# Shutdown.net
KiCad netlist of a schematic drawn in Altium Designer
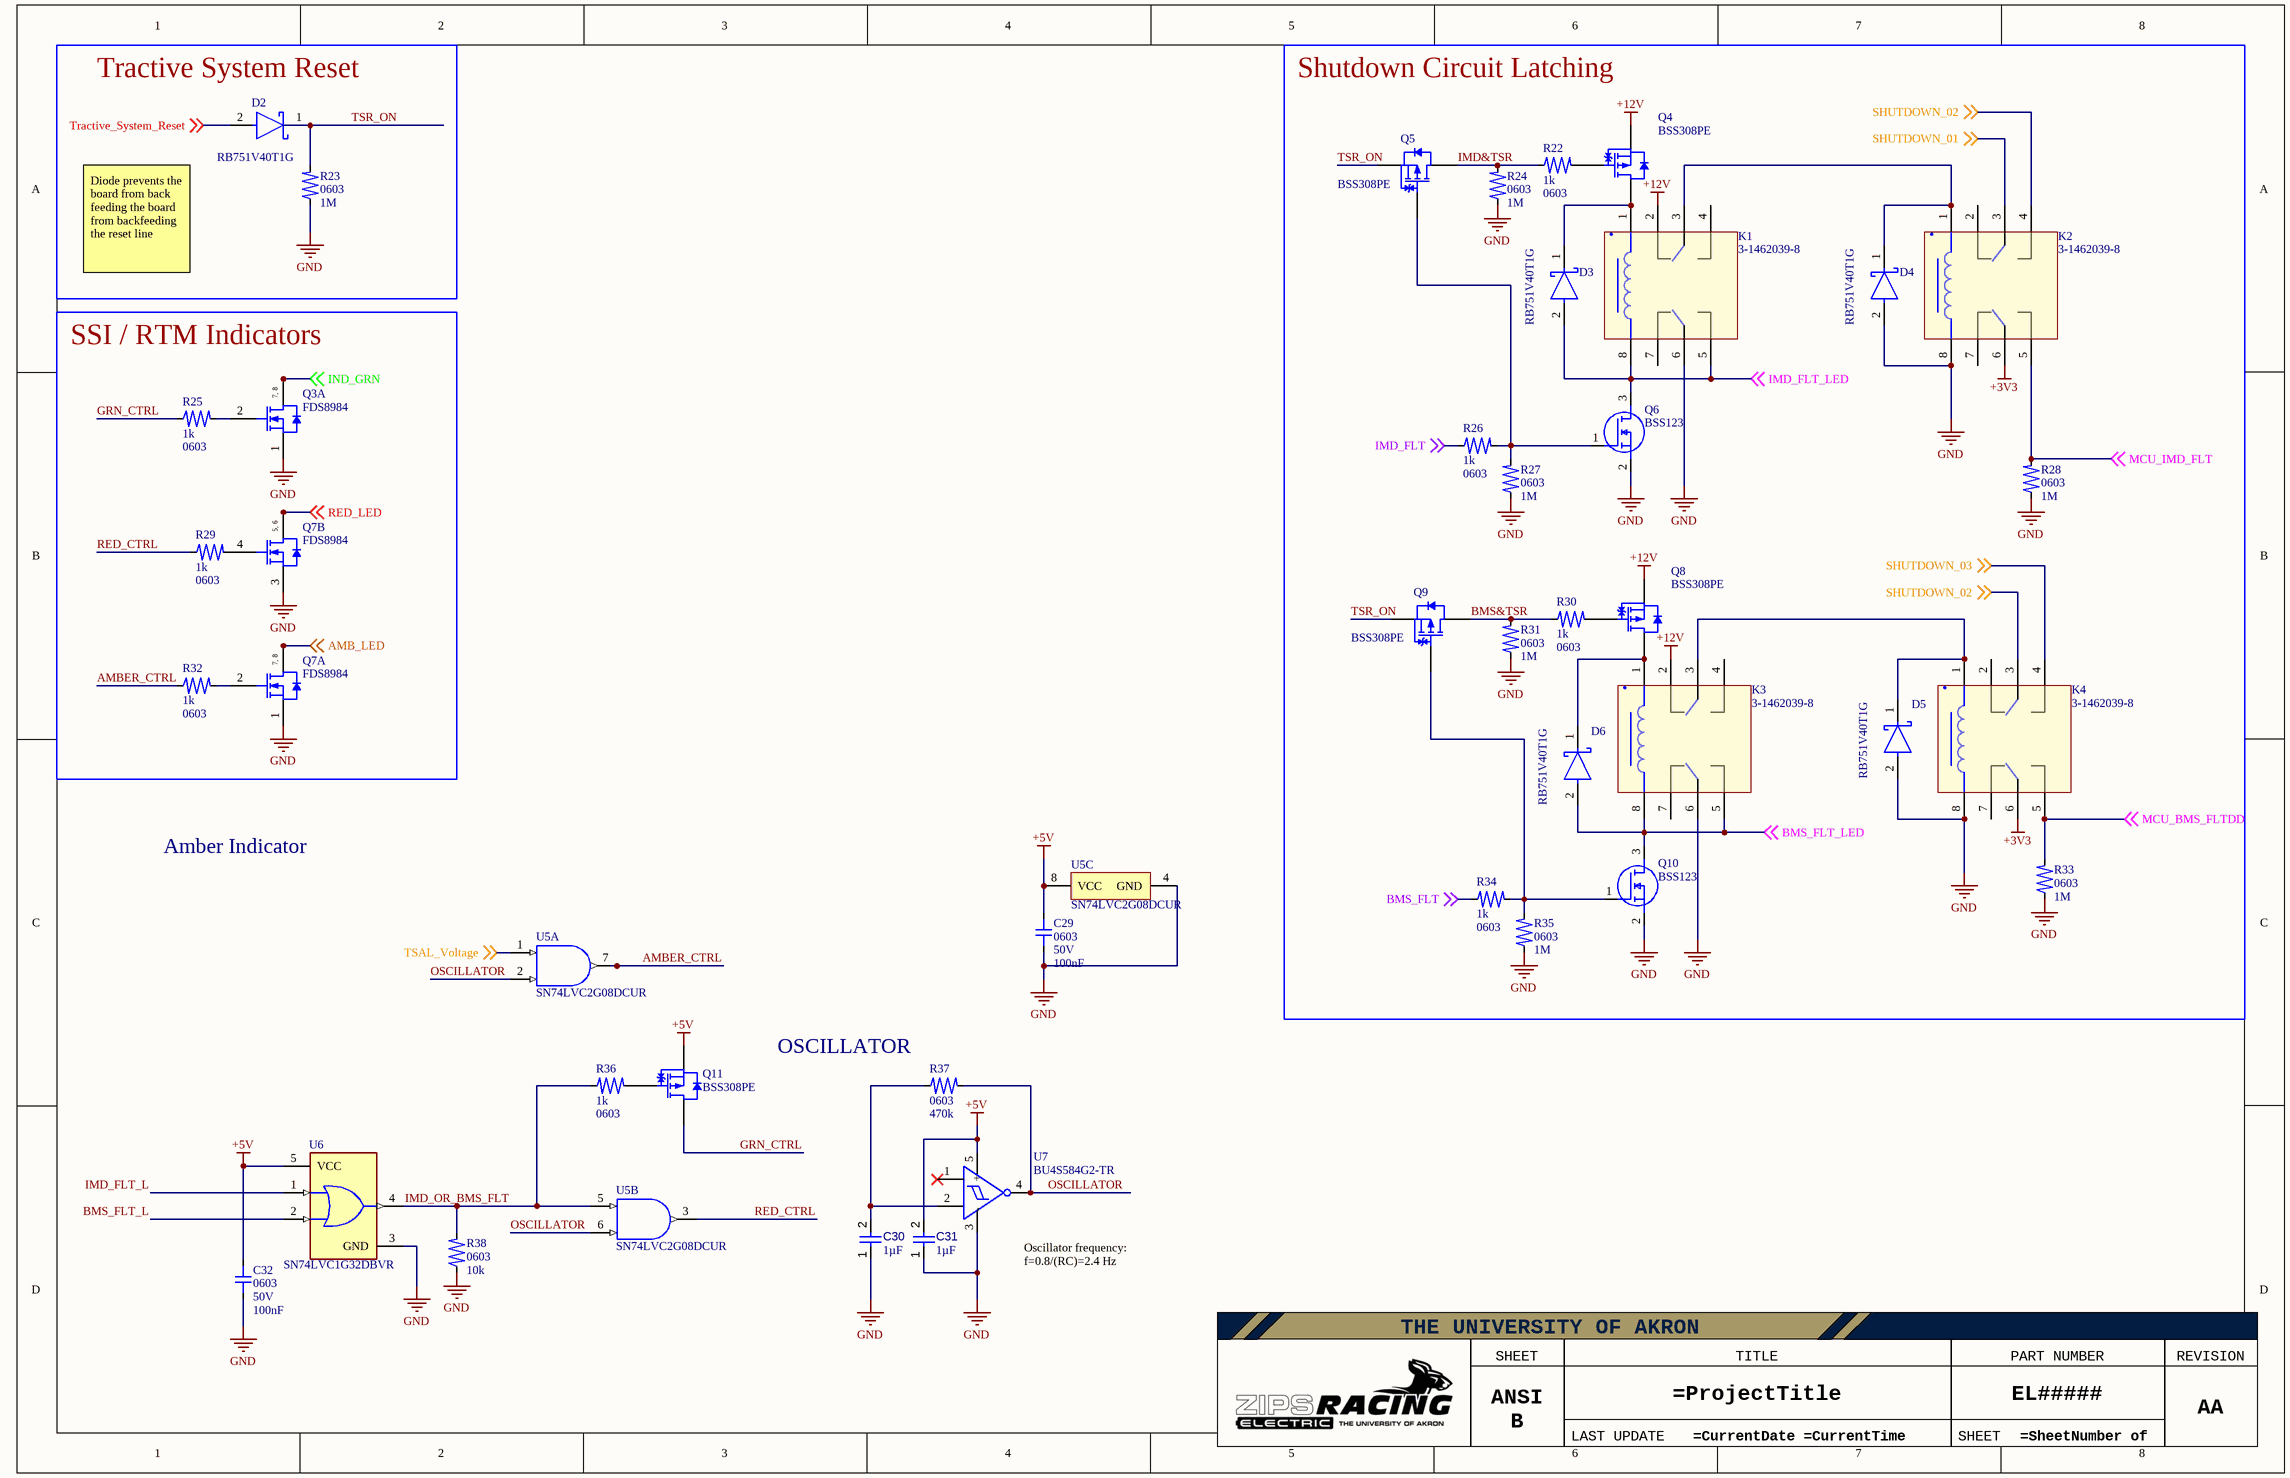
[diagram p0: Shutdown.SchDoc]

(export (version "E")
  (design (tool "Eeschema 10.0.6"))
  (components
    (comp (ref "C29")
      (value "100nF")
      (footprint "0603")
      (description "Capacitor, 0603, 5%")
      (fields (field (name "VOLTAGE") "50V") (field (name "Comment") "Capacitor 100nF 0603 5%"))
      (libsource (lib "Zips Racing Electric") (part "CAP-0603"))
    )
    (comp (ref "C30")
      (value "1µF")
      (footprint "CAPC1608X94X35NL15T15")
      (description "Chip Capacitor, 1 uF, +/- 10%, 16 V, 0603 (1608 Metric)")
      (fields (field (name "TOLERANCE") "10%") (field (name "Comment") "Capacitor 1 uF +/- 10% 16 V 0603"))
      (libsource (lib "Zips Racing Electric") (part "CAP-NP-2"))
    )
    (comp (ref "C31")
      (value "1µF")
      (footprint "CAPC1608X94X35NL15T15")
      (description "Chip Capacitor, 1 uF, +/- 10%, 16 V, 0603 (1608 Metric)")
      (fields (field (name "TOLERANCE") "10%") (field (name "Comment") "Capacitor 1 uF +/- 10% 16 V 0603"))
      (libsource (lib "Zips Racing Electric") (part "CAP-NP-2"))
    )
    (comp (ref "C32")
      (value "100nF")
      (footprint "0603")
      (description "Capacitor, 0603, 5%")
      (fields (field (name "VOLTAGE") "50V") (field (name "Comment") "Capacitor 100nF 0603 5%"))
      (libsource (lib "Zips Racing Electric") (part "CAP-0603"))
    )
    (comp (ref "D2")
      (value "RB751V40T1G")
      (footprint "FP-477-02-MFG")
      (description "Rectifier Diode, Schottky, 1 Phase, 1 Element, 0.03A, 40V V(RRM), Silicon")
      (libsource (lib "Zips Racing Electric") (part "1d6ec82d83fb6aee721767c19dac4b9"))
    )
    (comp (ref "D3")
      (value "RB751V40T1G")
      (footprint "FP-477-02-MFG")
      (description "Rectifier Diode, Schottky, 1 Phase, 1 Element, 0.03A, 40V V(RRM), Silicon")
      (libsource (lib "Zips Racing Electric") (part "1d6ec82d83fb6aee721767c19dac4b9"))
    )
    (comp (ref "D4")
      (value "RB751V40T1G")
      (footprint "FP-477-02-MFG")
      (description "Rectifier Diode, Schottky, 1 Phase, 1 Element, 0.03A, 40V V(RRM), Silicon")
      (libsource (lib "Zips Racing Electric") (part "1d6ec82d83fb6aee721767c19dac4b9"))
    )
    (comp (ref "D5")
      (value "RB751V40T1G")
      (footprint "FP-477-02-MFG")
      (description "Rectifier Diode, Schottky, 1 Phase, 1 Element, 0.03A, 40V V(RRM), Silicon")
      (libsource (lib "Zips Racing Electric") (part "1d6ec82d83fb6aee721767c19dac4b9"))
    )
    (comp (ref "D6")
      (value "RB751V40T1G")
      (footprint "FP-477-02-MFG")
      (description "Rectifier Diode, Schottky, 1 Phase, 1 Element, 0.03A, 40V V(RRM), Silicon")
      (libsource (lib "Zips Racing Electric") (part "1d6ec82d83fb6aee721767c19dac4b9"))
    )
    (comp (ref "K1")
      (value "3-1462039-8")
      (footprint "FP-3-1462039-8-MFG")
      (libsource (lib "Zips Racing Electric") (part "f6f6c627aadb73ad41e05903558ffa9"))
    )
    (comp (ref "K2")
      (value "3-1462039-8")
      (footprint "FP-3-1462039-8-MFG")
      (libsource (lib "Zips Racing Electric") (part "f6f6c627aadb73ad41e05903558ffa9"))
    )
    (comp (ref "K3")
      (value "3-1462039-8")
      (footprint "FP-3-1462039-8-MFG")
      (libsource (lib "Zips Racing Electric") (part "f6f6c627aadb73ad41e05903558ffa9"))
    )
    (comp (ref "K4")
      (value "3-1462039-8")
      (footprint "FP-3-1462039-8-MFG")
      (libsource (lib "Zips Racing Electric") (part "f6f6c627aadb73ad41e05903558ffa9"))
    )
    (comp (ref "Q3")
      (value "FDS8984")
      (footprint "FAIR-SOIC-8_V")
      (libsource (lib "Zips Racing Electric") (part "NEMOS-SGDD-SGDD-8"))
    )
    (comp (ref "Q4")
      (value "BSS308PE")
      (footprint "INF-PG-SOT23_M")
      (libsource (lib "Zips Racing Electric") (part "INF-BSS3XXPE-PG-SOT23-3"))
    )
    (comp (ref "Q5")
      (value "BSS308PE")
      (footprint "INF-PG-SOT23_M")
      (libsource (lib "Zips Racing Electric") (part "INF-BSS3XXPE-PG-SOT23-3"))
    )
    (comp (ref "Q6")
      (value "BSS123")
      (footprint "SOT96P237X111-3N")
      (description "MOSFET N-CH 100V 170MA SOT23-3")
      (fields
        (field (name "MOUSER PART NUMBER") "512-BSS123")
        (field (name "SOURCE") "Zips_Racing_Electric.SchLib")
      )
      (libsource (lib "Zips Racing Electric") (part "BSS123"))
    )
    (comp (ref "Q7")
      (value "FDS8984")
      (footprint "FAIR-SOIC-8_V")
      (libsource (lib "Zips Racing Electric") (part "NEMOS-SGDD-SGDD-8"))
    )
    (comp (ref "Q8")
      (value "BSS308PE")
      (footprint "INF-PG-SOT23_M")
      (libsource (lib "Zips Racing Electric") (part "INF-BSS3XXPE-PG-SOT23-3"))
    )
    (comp (ref "Q9")
      (value "BSS308PE")
      (footprint "INF-PG-SOT23_M")
      (libsource (lib "Zips Racing Electric") (part "INF-BSS3XXPE-PG-SOT23-3"))
    )
    (comp (ref "Q10")
      (value "BSS123")
      (footprint "SOT96P237X111-3N")
      (description "MOSFET N-CH 100V 170MA SOT23-3")
      (fields
        (field (name "MOUSER PART NUMBER") "512-BSS123")
        (field (name "SOURCE") "Zips_Racing_Electric.SchLib")
      )
      (libsource (lib "Zips Racing Electric") (part "BSS123"))
    )
    (comp (ref "Q11")
      (value "BSS308PE")
      (footprint "INF-PG-SOT23_M")
      (libsource (lib "Zips Racing Electric") (part "INF-BSS3XXPE-PG-SOT23-3"))
    )
    (comp (ref "R22")
      (value "1k")
      (footprint "0603")
      (description "Resistor, 0603, 1k")
      (fields (field (name "POWER") "100mW") (field (name "TOLERANCE") "1%"))
      (libsource (lib "Zips Racing Electric") (part "RES-0603"))
    )
    (comp (ref "R23")
      (value "1M")
      (footprint "0603")
      (description "Resistor, 0603, 1%, 1/10W")
      (fields (field (name "TOLERANCE") "1%") (field (name "POWER") "100mW"))
      (libsource (lib "Zips Racing Electric") (part "RES-0603"))
    )
    (comp (ref "R24")
      (value "1M")
      (footprint "0603")
      (description "Resistor, 0603, 1%, 1/10W")
      (fields (field (name "TOLERANCE") "1%") (field (name "POWER") "100mW"))
      (libsource (lib "Zips Racing Electric") (part "RES-0603"))
    )
    (comp (ref "R25")
      (value "1k")
      (footprint "0603")
      (description "Resistor, 0603, 1k")
      (fields (field (name "POWER") "100mW") (field (name "TOLERANCE") "1%"))
      (libsource (lib "Zips Racing Electric") (part "RES-0603"))
    )
    (comp (ref "R26")
      (value "1k")
      (footprint "0603")
      (description "Resistor, 0603, 1k")
      (fields (field (name "POWER") "100mW") (field (name "TOLERANCE") "1%"))
      (libsource (lib "Zips Racing Electric") (part "RES-0603"))
    )
    (comp (ref "R27")
      (value "1M")
      (footprint "0603")
      (description "Resistor, 0603, 1%, 1/10W")
      (fields (field (name "TOLERANCE") "1%") (field (name "POWER") "100mW"))
      (libsource (lib "Zips Racing Electric") (part "RES-0603"))
    )
    (comp (ref "R28")
      (value "1M")
      (footprint "0603")
      (description "Resistor, 0603, 1%, 1/10W")
      (fields (field (name "TOLERANCE") "1%") (field (name "POWER") "100mW"))
      (libsource (lib "Zips Racing Electric") (part "RES-0603"))
    )
    (comp (ref "R29")
      (value "1k")
      (footprint "0603")
      (description "Resistor, 0603, 1k")
      (fields (field (name "POWER") "100mW") (field (name "TOLERANCE") "1%"))
      (libsource (lib "Zips Racing Electric") (part "RES-0603"))
    )
    (comp (ref "R30")
      (value "1k")
      (footprint "0603")
      (description "Resistor, 0603, 1k")
      (fields (field (name "POWER") "100mW") (field (name "TOLERANCE") "1%"))
      (libsource (lib "Zips Racing Electric") (part "RES-0603"))
    )
    (comp (ref "R31")
      (value "1M")
      (footprint "0603")
      (description "Resistor, 0603, 1%, 1/10W")
      (fields (field (name "TOLERANCE") "1%") (field (name "POWER") "100mW"))
      (libsource (lib "Zips Racing Electric") (part "RES-0603"))
    )
    (comp (ref "R32")
      (value "1k")
      (footprint "0603")
      (description "Resistor, 0603, 1k")
      (fields (field (name "POWER") "100mW") (field (name "TOLERANCE") "1%"))
      (libsource (lib "Zips Racing Electric") (part "RES-0603"))
    )
    (comp (ref "R33")
      (value "1M")
      (footprint "0603")
      (description "Resistor, 0603, 1%, 1/10W")
      (fields (field (name "TOLERANCE") "1%") (field (name "POWER") "100mW"))
      (libsource (lib "Zips Racing Electric") (part "RES-0603"))
    )
    (comp (ref "R34")
      (value "1k")
      (footprint "0603")
      (description "Resistor, 0603, 1k")
      (fields (field (name "POWER") "100mW") (field (name "TOLERANCE") "1%"))
      (libsource (lib "Zips Racing Electric") (part "RES-0603"))
    )
    (comp (ref "R35")
      (value "1M")
      (footprint "0603")
      (description "Resistor, 0603, 1%, 1/10W")
      (fields (field (name "TOLERANCE") "1%") (field (name "POWER") "100mW"))
      (libsource (lib "Zips Racing Electric") (part "RES-0603"))
    )
    (comp (ref "R36")
      (value "1k")
      (footprint "0603")
      (description "Resistor, 0603, 1k")
      (fields (field (name "POWER") "100mW") (field (name "TOLERANCE") "1%"))
      (libsource (lib "Zips Racing Electric") (part "RES-0603"))
    )
    (comp (ref "R37")
      (value "470k")
      (footprint "0603")
      (description "Resistor, 0603, 1%, 1/10W")
      (fields (field (name "POWER") "100mW") (field (name "TOLERANCE") "1%"))
      (libsource (lib "Zips Racing Electric") (part "RES-0603"))
    )
    (comp (ref "R38")
      (value "10k")
      (footprint "0603")
      (description "Resistor, 0603, 10k")
      (fields (field (name "TOLERANCE") "1%") (field (name "POWER") "100mW"))
      (libsource (lib "Zips Racing Electric") (part "RES-0603"))
    )
    (comp (ref "U5")
      (value "SN74LVC2G08DCUR")
      (footprint "DCU0008A_N")
      (description "AND Gate, LVC/LCX/Z Series, 2-Func, 2-Input, CMOS, PDSO8")
      (libsource (lib "Zips Racing Electric") (part "TI-SN74XXX2G08-8"))
    )
    (comp (ref "U6")
      (value "SN74LVC1G32DBVR")
      (footprint "FP-DBV0005A-MFG")
      (description "OR Gate, LVC/LCX/Z Series, 1-Func, 2-Input, CMOS, PDSO5")
      (libsource (lib "Zips Racing Electric") (part "2d45b965ba21b0e9f05d619e439b306"))
    )
    (comp (ref "U7")
      (value "BU4S584G2-TR")
      (footprint "SSOP5_ROM")
      (description "Inverter IC 1 Channel Schmitt Trigger 5-SSOP")
      (fields
        (field (name "COPYRIGHT") "Copyright (C) 2021 Ultra Librarian. All rights reserved.")
        (field (name "SOURCE") "Zips_Racing_Electric.SchLib")
      )
      (libsource (lib "Zips Racing Electric") (part "BU4S584G2-TR"))
    )
  )
  (nets
    (net (code "1") (name "+3V3") (class "Default")
      (node (ref "K2") (pin "6") (pinfunction "6_6") (pintype "passive"))
      (node (ref "K4") (pin "6") (pinfunction "6_6") (pintype "passive"))
    )
    (net (code "2") (name "+5V") (class "Default")
      (node (ref "C29") (pin "2") (pinfunction "2_2") (pintype "passive"))
      (node (ref "C31") (pin "2") (pinfunction "2_2") (pintype "passive"))
      (node (ref "C32") (pin "2") (pinfunction "2_2") (pintype "passive"))
      (node (ref "Q11") (pin "2") (pinfunction "SOURCE_2") (pintype "passive"))
      (node (ref "U5") (pin "8") (pinfunction "VCC_8") (pintype "power_in"))
      (node (ref "U6") (pin "5") (pinfunction "VCC_5") (pintype "power_in"))
      (node (ref "U7") (pin "5") (pinfunction "+_5") (pintype "passive"))
    )
    (net (code "3") (name "+12V") (class "Default")
      (node (ref "K1") (pin "2") (pinfunction "2_2") (pintype "passive"))
      (node (ref "K3") (pin "2") (pinfunction "2_2") (pintype "passive"))
      (node (ref "Q4") (pin "2") (pinfunction "SOURCE_2") (pintype "passive"))
      (node (ref "Q8") (pin "2") (pinfunction "SOURCE_2") (pintype "passive"))
    )
    (net (code "4") (name "/AMBER_CTRL") (class "Default")
      (node (ref "R32") (pin "1") (pinfunction "1_1") (pintype "passive"))
      (node (ref "U5") (pin "7") (pinfunction "1Y_7") (pintype "output"))
    )
    (net (code "5") (name "/BMS&TSR") (class "Default")
      (node (ref "Q9") (pin "3") (pinfunction "DRAIN_3") (pintype "passive"))
      (node (ref "R30") (pin "1") (pinfunction "1_1") (pintype "passive"))
      (node (ref "R31") (pin "2") (pinfunction "2_2") (pintype "passive"))
    )
    (net (code "6") (name "/BMS_FLT_L") (class "Default")
      (node (ref "U6") (pin "2") (pinfunction "B_2") (pintype "input"))
    )
    (net (code "7") (name "/GRN_CTRL") (class "Default")
      (node (ref "Q11") (pin "3") (pinfunction "DRAIN_3") (pintype "passive"))
      (node (ref "R25") (pin "1") (pinfunction "1_1") (pintype "passive"))
    )
    (net (code "8") (name "/IMD&TSR") (class "Default")
      (node (ref "Q5") (pin "3") (pinfunction "DRAIN_3") (pintype "passive"))
      (node (ref "R22") (pin "1") (pinfunction "1_1") (pintype "passive"))
      (node (ref "R24") (pin "2") (pinfunction "2_2") (pintype "passive"))
    )
    (net (code "9") (name "/IMD_FLT_L") (class "Default")
      (node (ref "U6") (pin "1") (pinfunction "A_1") (pintype "input"))
    )
    (net (code "10") (name "/IMD_OR_BMS_FLT") (class "Default")
      (node (ref "R36") (pin "1") (pinfunction "1_1") (pintype "passive"))
      (node (ref "R38") (pin "2") (pinfunction "2_2") (pintype "passive"))
      (node (ref "U5") (pin "5") (pinfunction "2A_5") (pintype "input"))
      (node (ref "U6") (pin "4") (pinfunction "Y_4") (pintype "output"))
    )
    (net (code "11") (name "/OSCILLATOR") (class "Default")
      (node (ref "R37") (pin "2") (pinfunction "2_2") (pintype "passive"))
      (node (ref "U5") (pin "2") (pinfunction "1B_2") (pintype "input"))
      (node (ref "U5") (pin "6") (pinfunction "2B_6") (pintype "input"))
      (node (ref "U7") (pin "4") (pinfunction "4_4") (pintype "passive"))
    )
    (net (code "12") (name "/RED_CTRL") (class "Default")
      (node (ref "R29") (pin "1") (pinfunction "1_1") (pintype "passive"))
      (node (ref "U5") (pin "3") (pinfunction "2Y_3") (pintype "output"))
    )
    (net (code "13") (name "/TSR_ON") (class "Default")
      (node (ref "D2") (pin "1") (pinfunction "C_1") (pintype "passive"))
      (node (ref "Q5") (pin "2") (pinfunction "SOURCE_2") (pintype "passive"))
      (node (ref "Q9") (pin "2") (pinfunction "SOURCE_2") (pintype "passive"))
      (node (ref "R23") (pin "2") (pinfunction "2_2") (pintype "passive"))
    )
    (net (code "14") (name "AMB_LED") (class "Default")
      (node (ref "Q7") (pin "7") (pinfunction "D1_7") (pintype "passive"))
      (node (ref "Q7") (pin "8") (pinfunction "D1_8") (pintype "passive"))
    )
    (net (code "15") (name "BMS_FLT") (class "Default")
      (node (ref "R34") (pin "1") (pinfunction "1_1") (pintype "passive"))
    )
    (net (code "16") (name "BMS_FLT_LED") (class "Default")
      (node (ref "D6") (pin "2") (pinfunction "A_2") (pintype "passive"))
      (node (ref "K3") (pin "5") (pinfunction "5_5") (pintype "passive"))
      (node (ref "K3") (pin "8") (pinfunction "8_8") (pintype "passive"))
      (node (ref "Q10") (pin "3") (pinfunction "D_3") (pintype "passive"))
    )
    (net (code "17") (name "GND") (class "Default")
      (node (ref "C29") (pin "1") (pinfunction "1_1") (pintype "passive"))
      (node (ref "C30") (pin "1") (pinfunction "1_1") (pintype "passive"))
      (node (ref "C31") (pin "1") (pinfunction "1_1") (pintype "passive"))
      (node (ref "C32") (pin "1") (pinfunction "1_1") (pintype "passive"))
      (node (ref "D4") (pin "2") (pinfunction "A_2") (pintype "passive"))
      (node (ref "D5") (pin "2") (pinfunction "A_2") (pintype "passive"))
      (node (ref "K1") (pin "6") (pinfunction "6_6") (pintype "passive"))
      (node (ref "K2") (pin "8") (pinfunction "8_8") (pintype "passive"))
      (node (ref "K3") (pin "6") (pinfunction "6_6") (pintype "passive"))
      (node (ref "K4") (pin "8") (pinfunction "8_8") (pintype "passive"))
      (node (ref "Q10") (pin "2") (pinfunction "S_2") (pintype "passive"))
      (node (ref "Q3") (pin "1") (pinfunction "S1_1") (pintype "passive"))
      (node (ref "Q6") (pin "2") (pinfunction "S_2") (pintype "passive"))
      (node (ref "Q7") (pin "1") (pinfunction "S1_1") (pintype "passive"))
      (node (ref "Q7") (pin "3") (pinfunction "S2_3") (pintype "passive"))
      (node (ref "R23") (pin "1") (pinfunction "1_1") (pintype "passive"))
      (node (ref "R24") (pin "1") (pinfunction "1_1") (pintype "passive"))
      (node (ref "R27") (pin "1") (pinfunction "1_1") (pintype "passive"))
      (node (ref "R28") (pin "1") (pinfunction "1_1") (pintype "passive"))
      (node (ref "R31") (pin "1") (pinfunction "1_1") (pintype "passive"))
      (node (ref "R33") (pin "1") (pinfunction "1_1") (pintype "passive"))
      (node (ref "R35") (pin "1") (pinfunction "1_1") (pintype "passive"))
      (node (ref "R38") (pin "1") (pinfunction "1_1") (pintype "passive"))
      (node (ref "U5") (pin "4") (pinfunction "GND_4") (pintype "power_in"))
      (node (ref "U6") (pin "3") (pinfunction "GND_3") (pintype "power_in"))
      (node (ref "U7") (pin "3") (pinfunction "-_3") (pintype "passive"))
    )
    (net (code "18") (name "IMD_FLT") (class "Default")
      (node (ref "R26") (pin "1") (pinfunction "1_1") (pintype "passive"))
    )
    (net (code "19") (name "IMD_FLT_LED") (class "Default")
      (node (ref "D3") (pin "2") (pinfunction "A_2") (pintype "passive"))
      (node (ref "K1") (pin "5") (pinfunction "5_5") (pintype "passive"))
      (node (ref "K1") (pin "8") (pinfunction "8_8") (pintype "passive"))
      (node (ref "Q6") (pin "3") (pinfunction "D_3") (pintype "passive"))
    )
    (net (code "20") (name "IND_GRN") (class "Default")
      (node (ref "Q3") (pin "7") (pinfunction "D1_7") (pintype "passive"))
      (node (ref "Q3") (pin "8") (pinfunction "D1_8") (pintype "passive"))
    )
    (net (code "21") (name "MCU_BMS_FLTDD") (class "Default")
      (node (ref "K4") (pin "5") (pinfunction "5_5") (pintype "passive"))
      (node (ref "R33") (pin "2") (pinfunction "2_2") (pintype "passive"))
    )
    (net (code "22") (name "MCU_IMD_FLT") (class "Default")
      (node (ref "K2") (pin "5") (pinfunction "5_5") (pintype "passive"))
      (node (ref "R28") (pin "2") (pinfunction "2_2") (pintype "passive"))
    )
    (net (code "23") (name "Net-(C30-Pad2)") (class "Default")
      (node (ref "C30") (pin "2") (pinfunction "2_2") (pintype "passive"))
      (node (ref "R37") (pin "1") (pinfunction "1_1") (pintype "passive"))
      (node (ref "U7") (pin "2") (pinfunction "2_2") (pintype "passive"))
    )
    (net (code "24") (name "Net-(D3-C)") (class "Default")
      (node (ref "D3") (pin "1") (pinfunction "C_1") (pintype "passive"))
      (node (ref "K1") (pin "1") (pinfunction "1_1") (pintype "passive"))
      (node (ref "Q4") (pin "3") (pinfunction "DRAIN_3") (pintype "passive"))
    )
    (net (code "25") (name "Net-(D4-C)") (class "Default")
      (node (ref "D4") (pin "1") (pinfunction "C_1") (pintype "passive"))
      (node (ref "K1") (pin "3") (pinfunction "3_3") (pintype "passive"))
      (node (ref "K2") (pin "1") (pinfunction "1_1") (pintype "passive"))
    )
    (net (code "26") (name "Net-(D5-C)") (class "Default")
      (node (ref "D5") (pin "1") (pinfunction "C_1") (pintype "passive"))
      (node (ref "K3") (pin "3") (pinfunction "3_3") (pintype "passive"))
      (node (ref "K4") (pin "1") (pinfunction "1_1") (pintype "passive"))
    )
    (net (code "27") (name "Net-(D6-C)") (class "Default")
      (node (ref "D6") (pin "1") (pinfunction "C_1") (pintype "passive"))
      (node (ref "K3") (pin "1") (pinfunction "1_1") (pintype "passive"))
      (node (ref "Q8") (pin "3") (pinfunction "DRAIN_3") (pintype "passive"))
    )
    (net (code "28") (name "Net-(Q3A-G1)") (class "Default")
      (node (ref "Q3") (pin "2") (pinfunction "G1_2") (pintype "passive"))
      (node (ref "R25") (pin "2") (pinfunction "2_2") (pintype "passive"))
    )
    (net (code "29") (name "Net-(Q4-GATE)") (class "Default")
      (node (ref "Q4") (pin "1") (pinfunction "GATE_1") (pintype "passive"))
      (node (ref "R22") (pin "2") (pinfunction "2_2") (pintype "passive"))
    )
    (net (code "30") (name "Net-(Q5-GATE)") (class "Default")
      (node (ref "Q5") (pin "1") (pinfunction "GATE_1") (pintype "passive"))
      (node (ref "Q6") (pin "1") (pinfunction "G_1") (pintype "passive"))
      (node (ref "R26") (pin "2") (pinfunction "2_2") (pintype "passive"))
      (node (ref "R27") (pin "2") (pinfunction "2_2") (pintype "passive"))
    )
    (net (code "31") (name "Net-(Q7A-G1)") (class "Default")
      (node (ref "Q7") (pin "2") (pinfunction "G1_2") (pintype "passive"))
      (node (ref "R32") (pin "2") (pinfunction "2_2") (pintype "passive"))
    )
    (net (code "32") (name "Net-(Q7B-G2)") (class "Default")
      (node (ref "Q7") (pin "4") (pinfunction "G2_4") (pintype "passive"))
      (node (ref "R29") (pin "2") (pinfunction "2_2") (pintype "passive"))
    )
    (net (code "33") (name "Net-(Q8-GATE)") (class "Default")
      (node (ref "Q8") (pin "1") (pinfunction "GATE_1") (pintype "passive"))
      (node (ref "R30") (pin "2") (pinfunction "2_2") (pintype "passive"))
    )
    (net (code "34") (name "Net-(Q10-G)") (class "Default")
      (node (ref "Q10") (pin "1") (pinfunction "G_1") (pintype "passive"))
      (node (ref "Q9") (pin "1") (pinfunction "GATE_1") (pintype "passive"))
      (node (ref "R34") (pin "2") (pinfunction "2_2") (pintype "passive"))
      (node (ref "R35") (pin "2") (pinfunction "2_2") (pintype "passive"))
    )
    (net (code "35") (name "Net-(Q11-GATE)") (class "Default")
      (node (ref "Q11") (pin "1") (pinfunction "GATE_1") (pintype "passive"))
      (node (ref "R36") (pin "2") (pinfunction "2_2") (pintype "passive"))
    )
    (net (code "36") (name "RED_LED") (class "Default")
      (node (ref "Q7") (pin "5") (pinfunction "D2_5") (pintype "passive"))
      (node (ref "Q7") (pin "6") (pinfunction "D2_6") (pintype "passive"))
    )
    (net (code "37") (name "SHUTDOWN_01") (class "Default")
      (node (ref "K2") (pin "3") (pinfunction "3_3") (pintype "passive"))
    )
    (net (code "38") (name "SHUTDOWN_02") (class "Default")
      (node (ref "K2") (pin "4") (pinfunction "4_4") (pintype "passive"))
      (node (ref "K4") (pin "3") (pinfunction "3_3") (pintype "passive"))
    )
    (net (code "39") (name "SHUTDOWN_03") (class "Default")
      (node (ref "K4") (pin "4") (pinfunction "4_4") (pintype "passive"))
    )
    (net (code "40") (name "TSAL_Voltage") (class "Default")
      (node (ref "U5") (pin "1") (pinfunction "1A_1") (pintype "input"))
    )
    (net (code "41") (name "Tractive_System_Reset") (class "Default")
      (node (ref "D2") (pin "2") (pinfunction "A_2") (pintype "passive"))
    )
    (net (code "42") (name "unconnected-(K1-Pad4)") (class "Default")
      (node (ref "K1") (pin "4") (pinfunction "4_4") (pintype "passive"))
    )
    (net (code "43") (name "unconnected-(K1-Pad7)") (class "Default")
      (node (ref "K1") (pin "7") (pinfunction "7_7") (pintype "passive"))
    )
    (net (code "44") (name "unconnected-(K2-Pad2)") (class "Default")
      (node (ref "K2") (pin "2") (pinfunction "2_2") (pintype "passive"))
    )
    (net (code "45") (name "unconnected-(K2-Pad7)") (class "Default")
      (node (ref "K2") (pin "7") (pinfunction "7_7") (pintype "passive"))
    )
    (net (code "46") (name "unconnected-(K3-Pad4)") (class "Default")
      (node (ref "K3") (pin "4") (pinfunction "4_4") (pintype "passive"))
    )
    (net (code "47") (name "unconnected-(K3-Pad7)") (class "Default")
      (node (ref "K3") (pin "7") (pinfunction "7_7") (pintype "passive"))
    )
    (net (code "48") (name "unconnected-(K4-Pad2)") (class "Default")
      (node (ref "K4") (pin "2") (pinfunction "2_2") (pintype "passive"))
    )
    (net (code "49") (name "unconnected-(K4-Pad7)") (class "Default")
      (node (ref "K4") (pin "7") (pinfunction "7_7") (pintype "passive"))
    )
    (net (code "50") (name "unconnected-(U7-NC-Pad1)") (class "Default")
      (node (ref "U7") (pin "1") (pinfunction "NC_1") (pintype "passive+no_connect"))
    )
  )
)
